# UD3_1.net
KiCad netlist of a schematic drawn in Altium Designer
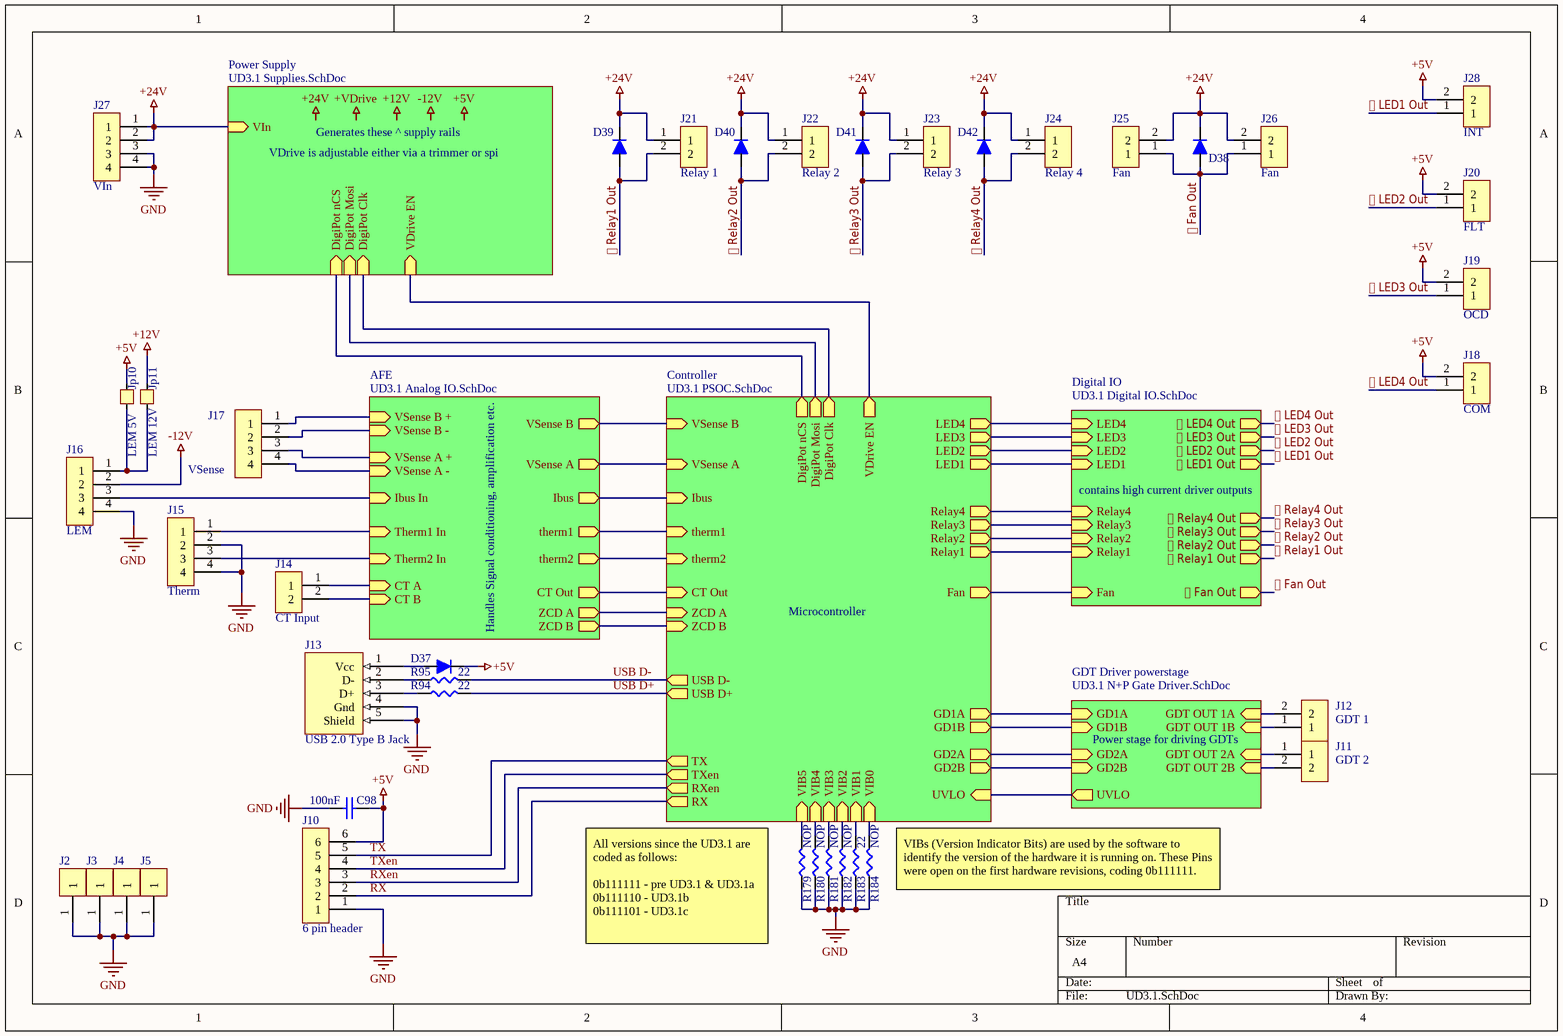
[diagram p0: UD3.1.SchDoc]

(export (version "E")
  (design (tool "Eeschema 10.0.6"))
  (components
    (comp (ref "C98") (value "100nF") (footprint "0603") (libsource (lib "stdLib") (part "Cap")))
    (comp (ref "D37")
      (value "Schottky 30V 1A")
      (footprint "DO-214")
      (description "Cmon its a diode what more do I need to say?")
      (libsource (lib "stdLib") (part "Diode"))
    )
    (comp (ref "D38")
      (value "Schottky 30V 1A")
      (footprint "DO-214")
      (description "Cmon its a diode what more do I need to say?")
      (libsource (lib "stdLib") (part "Diode"))
    )
    (comp (ref "D39")
      (value "Schottky 30V 100mA")
      (footprint "SOD523")
      (description "Cmon its a diode what more do I need to say?")
      (libsource (lib "stdLib") (part "Diode"))
    )
    (comp (ref "D40")
      (value "Schottky 30V 100mA")
      (footprint "SOD523")
      (description "Cmon its a diode what more do I need to say?")
      (libsource (lib "stdLib") (part "Diode"))
    )
    (comp (ref "D41")
      (value "Schottky 30V 100mA")
      (footprint "SOD523")
      (description "Cmon its a diode what more do I need to say?")
      (libsource (lib "stdLib") (part "Diode"))
    )
    (comp (ref "D42")
      (value "Schottky 30V 100mA")
      (footprint "SOD523")
      (description "Cmon its a diode what more do I need to say?")
      (libsource (lib "stdLib") (part "Diode"))
    )
    (comp (ref "J2") (value "GND Pad") (footprint "1 Pad M3") (libsource (lib "stdCon") (part "1 Header")))
    (comp (ref "J3") (value "GND Pad") (footprint "1 Pad M3") (libsource (lib "stdCon") (part "1 Header")))
    (comp (ref "J4") (value "GND Pad") (footprint "1 Pad M3") (libsource (lib "stdCon") (part "1 Header")))
    (comp (ref "J5") (value "GND Pad") (footprint "1 Pad M3") (libsource (lib "stdCon") (part "1 Header")))
    (comp (ref "J10")
      (value "6 pin header")
      (footprint "6 KK254 / KF2510")
      (libsource (lib "stdCon") (part "6 header"))
    )
    (comp (ref "J11") (value "GDT 2") (footprint "2 KK254 / KF2510") (libsource (lib "") (part "2 header_1")))
    (comp (ref "J12") (value "GDT 1") (footprint "2 KK254 / KF2510") (libsource (lib "") (part "2 header_2")))
    (comp (ref "J13")
      (value "USB 2.0 Type B Jack")
      (footprint "USB 2.0 Type B Vertical")
      (libsource (lib "stdCon") (part "USB 2.0 Type B"))
    )
    (comp (ref "J14")
      (value "CT Input")
      (footprint "2 KK254 / KF2510")
      (libsource (lib "stdCon") (part "2 header"))
    )
    (comp (ref "J15")
      (value "Therm")
      (footprint "4 KK254 / KF2510")
      (libsource (lib "stdCon") (part "4 header"))
    )
    (comp (ref "J16")
      (value "LEM")
      (footprint "4 KK254 / KF2510")
      (libsource (lib "stdCon") (part "4 header"))
    )
    (comp (ref "J17")
      (value "VSense")
      (footprint "4 KK254 / KF2510")
      (libsource (lib "stdCon") (part "4 header"))
    )
    (comp (ref "J18") (value "COM") (footprint "2 KK254 / KF2510") (libsource (lib "") (part "2 header_2")))
    (comp (ref "J19") (value "OCD") (footprint "2 KK254 / KF2510") (libsource (lib "") (part "2 header_2")))
    (comp (ref "J20") (value "FLT") (footprint "2 KK254 / KF2510") (libsource (lib "") (part "2 header_2")))
    (comp (ref "J21")
      (value "Relay 1")
      (footprint "2 KK254 / KF2510")
      (libsource (lib "") (part "2 header_1"))
    )
    (comp (ref "J22")
      (value "Relay 2")
      (footprint "2 KK254 / KF2510")
      (libsource (lib "") (part "2 header_1"))
    )
    (comp (ref "J23")
      (value "Relay 3")
      (footprint "2 KK254 / KF2510")
      (libsource (lib "") (part "2 header_1"))
    )
    (comp (ref "J24")
      (value "Relay 4")
      (footprint "2 KK254 / KF2510")
      (libsource (lib "") (part "2 header_1"))
    )
    (comp (ref "J25") (value "Fan") (footprint "2 KK254 / KF2510") (libsource (lib "") (part "2 header_3")))
    (comp (ref "J26")
      (value "Fan")
      (footprint "2 screw terminal vertical")
      (libsource (lib "stdCon") (part "2 screw terminal"))
    )
    (comp (ref "J27")
      (value "VIn")
      (footprint "4 KK254 / KF2510")
      (libsource (lib "stdCon") (part "4 header"))
    )
    (comp (ref "J28") (value "INT") (footprint "2 KK254 / KF2510") (libsource (lib "") (part "2 header_2")))
    (comp (ref "Jp10")
      (value "LEM 5V")
      (footprint "PCB Jumper NO")
      (libsource (lib "stdLib") (part "Jumper"))
    )
    (comp (ref "Jp11")
      (value "LEM 12V")
      (footprint "PCB Jumper NO")
      (libsource (lib "stdLib") (part "Jumper"))
    )
    (comp (ref "R94") (value "22") (footprint "0603") (libsource (lib "stdLib") (part "Resistor")))
    (comp (ref "R95") (value "22") (footprint "0603") (libsource (lib "stdLib") (part "Resistor")))
    (comp (ref "R179") (value "NOP") (footprint "0603") (libsource (lib "stdLib") (part "Resistor")))
    (comp (ref "R180") (value "NOP") (footprint "0603") (libsource (lib "stdLib") (part "Resistor")))
    (comp (ref "R181") (value "NOP") (footprint "0603") (libsource (lib "stdLib") (part "Resistor")))
    (comp (ref "R182") (value "NOP") (footprint "0603") (libsource (lib "stdLib") (part "Resistor")))
    (comp (ref "R183") (value "22") (footprint "0603") (libsource (lib "stdLib") (part "Resistor")))
    (comp (ref "R184") (value "NOP") (footprint "0603") (libsource (lib "stdLib") (part "Resistor")))
  )
  (nets
    (net (code "1") (name "+5V") (class "Default")
      (node (ref "C98") (pin "1") (pinfunction "1_1") (pintype "passive"))
      (node (ref "D37") (pin "2") (pintype "passive"))
      (node (ref "J10") (pin "6") (pinfunction "6_6") (pintype "passive"))
      (node (ref "J18") (pin "2") (pinfunction "2_2") (pintype "passive"))
      (node (ref "J19") (pin "2") (pinfunction "2_2") (pintype "passive"))
      (node (ref "J20") (pin "2") (pinfunction "2_2") (pintype "passive"))
      (node (ref "J28") (pin "2") (pinfunction "2_2") (pintype "passive"))
      (node (ref "Jp10") (pin "2") (pinfunction "2_2") (pintype "passive"))
    )
    (net (code "2") (name "+12V") (class "Default")
      (node (ref "Jp11") (pin "2") (pinfunction "2_2") (pintype "passive"))
    )
    (net (code "3") (name "+24V") (class "Default")
      (node (ref "D38") (pin "2") (pintype "passive"))
      (node (ref "D39") (pin "2") (pintype "passive"))
      (node (ref "D40") (pin "2") (pintype "passive"))
      (node (ref "D41") (pin "2") (pintype "passive"))
      (node (ref "D42") (pin "2") (pintype "passive"))
      (node (ref "J21") (pin "1") (pinfunction "1_1") (pintype "passive"))
      (node (ref "J22") (pin "1") (pinfunction "1_1") (pintype "passive"))
      (node (ref "J23") (pin "1") (pinfunction "1_1") (pintype "passive"))
      (node (ref "J24") (pin "1") (pinfunction "1_1") (pintype "passive"))
      (node (ref "J25") (pin "2") (pinfunction "2_2") (pintype "passive"))
      (node (ref "J26") (pin "2") (pinfunction "2_2") (pintype "passive"))
      (node (ref "J27") (pin "1") (pinfunction "1_1") (pintype "passive"))
      (node (ref "J27") (pin "2") (pinfunction "2_2") (pintype "passive"))
    )
    (net (code "5") (name "-12V") (class "Default")
      (node (ref "J16") (pin "2") (pinfunction "2_2") (pintype "passive"))
    )
    (net (code "6") (name "/CT A") (class "Default")
      (node (ref "J14") (pin "1") (pinfunction "1_1") (pintype "passive"))
    )
    (net (code "7") (name "/CT B") (class "Default")
      (node (ref "J14") (pin "2") (pinfunction "2_2") (pintype "passive"))
    )
    (net (code "17") (name "/GDT OUT 1A") (class "Default")
      (node (ref "J12") (pin "2") (pinfunction "2_2") (pintype "passive"))
    )
    (net (code "18") (name "/GDT OUT 1B") (class "Default")
      (node (ref "J12") (pin "1") (pinfunction "1_1") (pintype "passive"))
    )
    (net (code "19") (name "/GDT OUT 2A") (class "Default")
      (node (ref "J11") (pin "1") (pinfunction "1_1") (pintype "passive"))
    )
    (net (code "20") (name "/GDT OUT 2B") (class "Default")
      (node (ref "J11") (pin "2") (pinfunction "2_2") (pintype "passive"))
    )
    (net (code "22") (name "/Ibus In") (class "Default")
      (node (ref "J16") (pin "3") (pinfunction "3_3") (pintype "passive"))
    )
    (net (code "27") (name "/RX") (class "Default")
      (node (ref "J10") (pin "2") (pinfunction "2_2") (pintype "passive"))
    )
    (net (code "28") (name "/RXen") (class "Default")
      (node (ref "J10") (pin "3") (pinfunction "3_3") (pintype "passive"))
    )
    (net (code "33") (name "/TX") (class "Default")
      (node (ref "J10") (pin "5") (pinfunction "5_5") (pintype "passive"))
    )
    (net (code "34") (name "/TXen") (class "Default")
      (node (ref "J10") (pin "4") (pinfunction "4_4") (pintype "passive"))
    )
    (net (code "35") (name "/Therm1 In") (class "Default")
      (node (ref "J15") (pin "1") (pinfunction "1_1") (pintype "passive"))
    )
    (net (code "36") (name "/Therm2 In") (class "Default")
      (node (ref "J15") (pin "3") (pinfunction "3_3") (pintype "passive"))
    )
    (net (code "37") (name "/USB D+") (class "Default")
      (node (ref "R94") (pin "1") (pinfunction "1_1") (pintype "passive"))
    )
    (net (code "38") (name "/USB D-") (class "Default")
      (node (ref "R95") (pin "1") (pinfunction "1_1") (pintype "passive"))
    )
    (net (code "41") (name "/VIB0") (class "Default")
      (node (ref "R184") (pin "1") (pinfunction "1_1") (pintype "passive"))
    )
    (net (code "42") (name "/VIB1") (class "Default")
      (node (ref "R183") (pin "1") (pinfunction "1_1") (pintype "passive"))
    )
    (net (code "43") (name "/VIB2") (class "Default")
      (node (ref "R182") (pin "1") (pinfunction "1_1") (pintype "passive"))
    )
    (net (code "44") (name "/VIB3") (class "Default")
      (node (ref "R181") (pin "1") (pinfunction "1_1") (pintype "passive"))
    )
    (net (code "45") (name "/VIB4") (class "Default")
      (node (ref "R180") (pin "1") (pinfunction "1_1") (pintype "passive"))
    )
    (net (code "46") (name "/VIB5") (class "Default")
      (node (ref "R179") (pin "1") (pinfunction "1_1") (pintype "passive"))
    )
    (net (code "48") (name "/VSense A +") (class "Default")
      (node (ref "J17") (pin "3") (pinfunction "3_3") (pintype "passive"))
    )
    (net (code "49") (name "/VSense A -") (class "Default")
      (node (ref "J17") (pin "4") (pinfunction "4_4") (pintype "passive"))
    )
    (net (code "51") (name "/VSense B +") (class "Default")
      (node (ref "J17") (pin "1") (pinfunction "1_1") (pintype "passive"))
    )
    (net (code "52") (name "/VSense B -") (class "Default")
      (node (ref "J17") (pin "2") (pinfunction "2_2") (pintype "passive"))
    )
    (net (code "57") (name "/⎐ Fan Out") (class "Default")
      (node (ref "D38") (pin "1") (pintype "passive"))
      (node (ref "J25") (pin "1") (pinfunction "1_1") (pintype "passive"))
      (node (ref "J26") (pin "1") (pinfunction "1_1") (pintype "passive"))
    )
    (net (code "58") (name "/⎐ LED1 Out") (class "Default")
      (node (ref "J28") (pin "1") (pinfunction "1_1") (pintype "passive"))
    )
    (net (code "59") (name "/⎐ LED2 Out") (class "Default")
      (node (ref "J20") (pin "1") (pinfunction "1_1") (pintype "passive"))
    )
    (net (code "60") (name "/⎐ LED3 Out") (class "Default")
      (node (ref "J19") (pin "1") (pinfunction "1_1") (pintype "passive"))
    )
    (net (code "61") (name "/⎐ LED4 Out") (class "Default")
      (node (ref "J18") (pin "1") (pinfunction "1_1") (pintype "passive"))
    )
    (net (code "62") (name "/⎐ Relay1 Out") (class "Default")
      (node (ref "D39") (pin "1") (pintype "passive"))
      (node (ref "J21") (pin "2") (pinfunction "2_2") (pintype "passive"))
    )
    (net (code "63") (name "/⎐ Relay2 Out") (class "Default")
      (node (ref "D40") (pin "1") (pintype "passive"))
      (node (ref "J22") (pin "2") (pinfunction "2_2") (pintype "passive"))
    )
    (net (code "64") (name "/⎐ Relay3 Out") (class "Default")
      (node (ref "D41") (pin "1") (pintype "passive"))
      (node (ref "J23") (pin "2") (pinfunction "2_2") (pintype "passive"))
    )
    (net (code "65") (name "/⎐ Relay4 Out") (class "Default")
      (node (ref "D42") (pin "1") (pintype "passive"))
      (node (ref "J24") (pin "2") (pinfunction "2_2") (pintype "passive"))
    )
    (net (code "66") (name "GND") (class "Default")
      (node (ref "C98") (pin "2") (pinfunction "2_2") (pintype "passive"))
      (node (ref "J10") (pin "1") (pinfunction "1_1") (pintype "passive"))
      (node (ref "J13") (pin "4") (pinfunction "Gnd_4") (pintype "input"))
      (node (ref "J13") (pin "5") (pinfunction "Shield_5") (pintype "input"))
      (node (ref "J15") (pin "2") (pinfunction "2_2") (pintype "passive"))
      (node (ref "J15") (pin "4") (pinfunction "4_4") (pintype "passive"))
      (node (ref "J16") (pin "4") (pinfunction "4_4") (pintype "passive"))
      (node (ref "J2") (pin "1") (pinfunction "1_1") (pintype "passive"))
      (node (ref "J27") (pin "3") (pinfunction "3_3") (pintype "passive"))
      (node (ref "J27") (pin "4") (pinfunction "4_4") (pintype "passive"))
      (node (ref "J3") (pin "1") (pinfunction "1_1") (pintype "passive"))
      (node (ref "J4") (pin "1") (pinfunction "1_1") (pintype "passive"))
      (node (ref "J5") (pin "1") (pinfunction "1_1") (pintype "passive"))
      (node (ref "R179") (pin "2") (pinfunction "2_2") (pintype "passive"))
      (node (ref "R180") (pin "2") (pinfunction "2_2") (pintype "passive"))
      (node (ref "R181") (pin "2") (pinfunction "2_2") (pintype "passive"))
      (node (ref "R182") (pin "2") (pinfunction "2_2") (pintype "passive"))
      (node (ref "R183") (pin "2") (pinfunction "2_2") (pintype "passive"))
      (node (ref "R184") (pin "2") (pinfunction "2_2") (pintype "passive"))
    )
    (net (code "67") (name "Net-(J13-D+)") (class "Default")
      (node (ref "J13") (pin "3") (pinfunction "D+_3") (pintype "input"))
      (node (ref "R94") (pin "2") (pinfunction "2_2") (pintype "passive"))
    )
    (net (code "68") (name "Net-(J13-D-)") (class "Default")
      (node (ref "J13") (pin "2") (pinfunction "D-_2") (pintype "input"))
      (node (ref "R95") (pin "2") (pinfunction "2_2") (pintype "passive"))
    )
    (net (code "69") (name "Net-(J13-Vcc)") (class "Default")
      (node (ref "D37") (pin "1") (pintype "passive"))
      (node (ref "J13") (pin "1") (pinfunction "Vcc_1") (pintype "input"))
    )
    (net (code "70") (name "Net-(J16-Pad1)") (class "Default")
      (node (ref "J16") (pin "1") (pinfunction "1_1") (pintype "passive"))
      (node (ref "Jp10") (pin "1") (pinfunction "1_1") (pintype "passive"))
      (node (ref "Jp11") (pin "1") (pinfunction "1_1") (pintype "passive"))
    )
  )
)
